# music_box.net
KiCad netlist of a schematic drawn in EAGLE
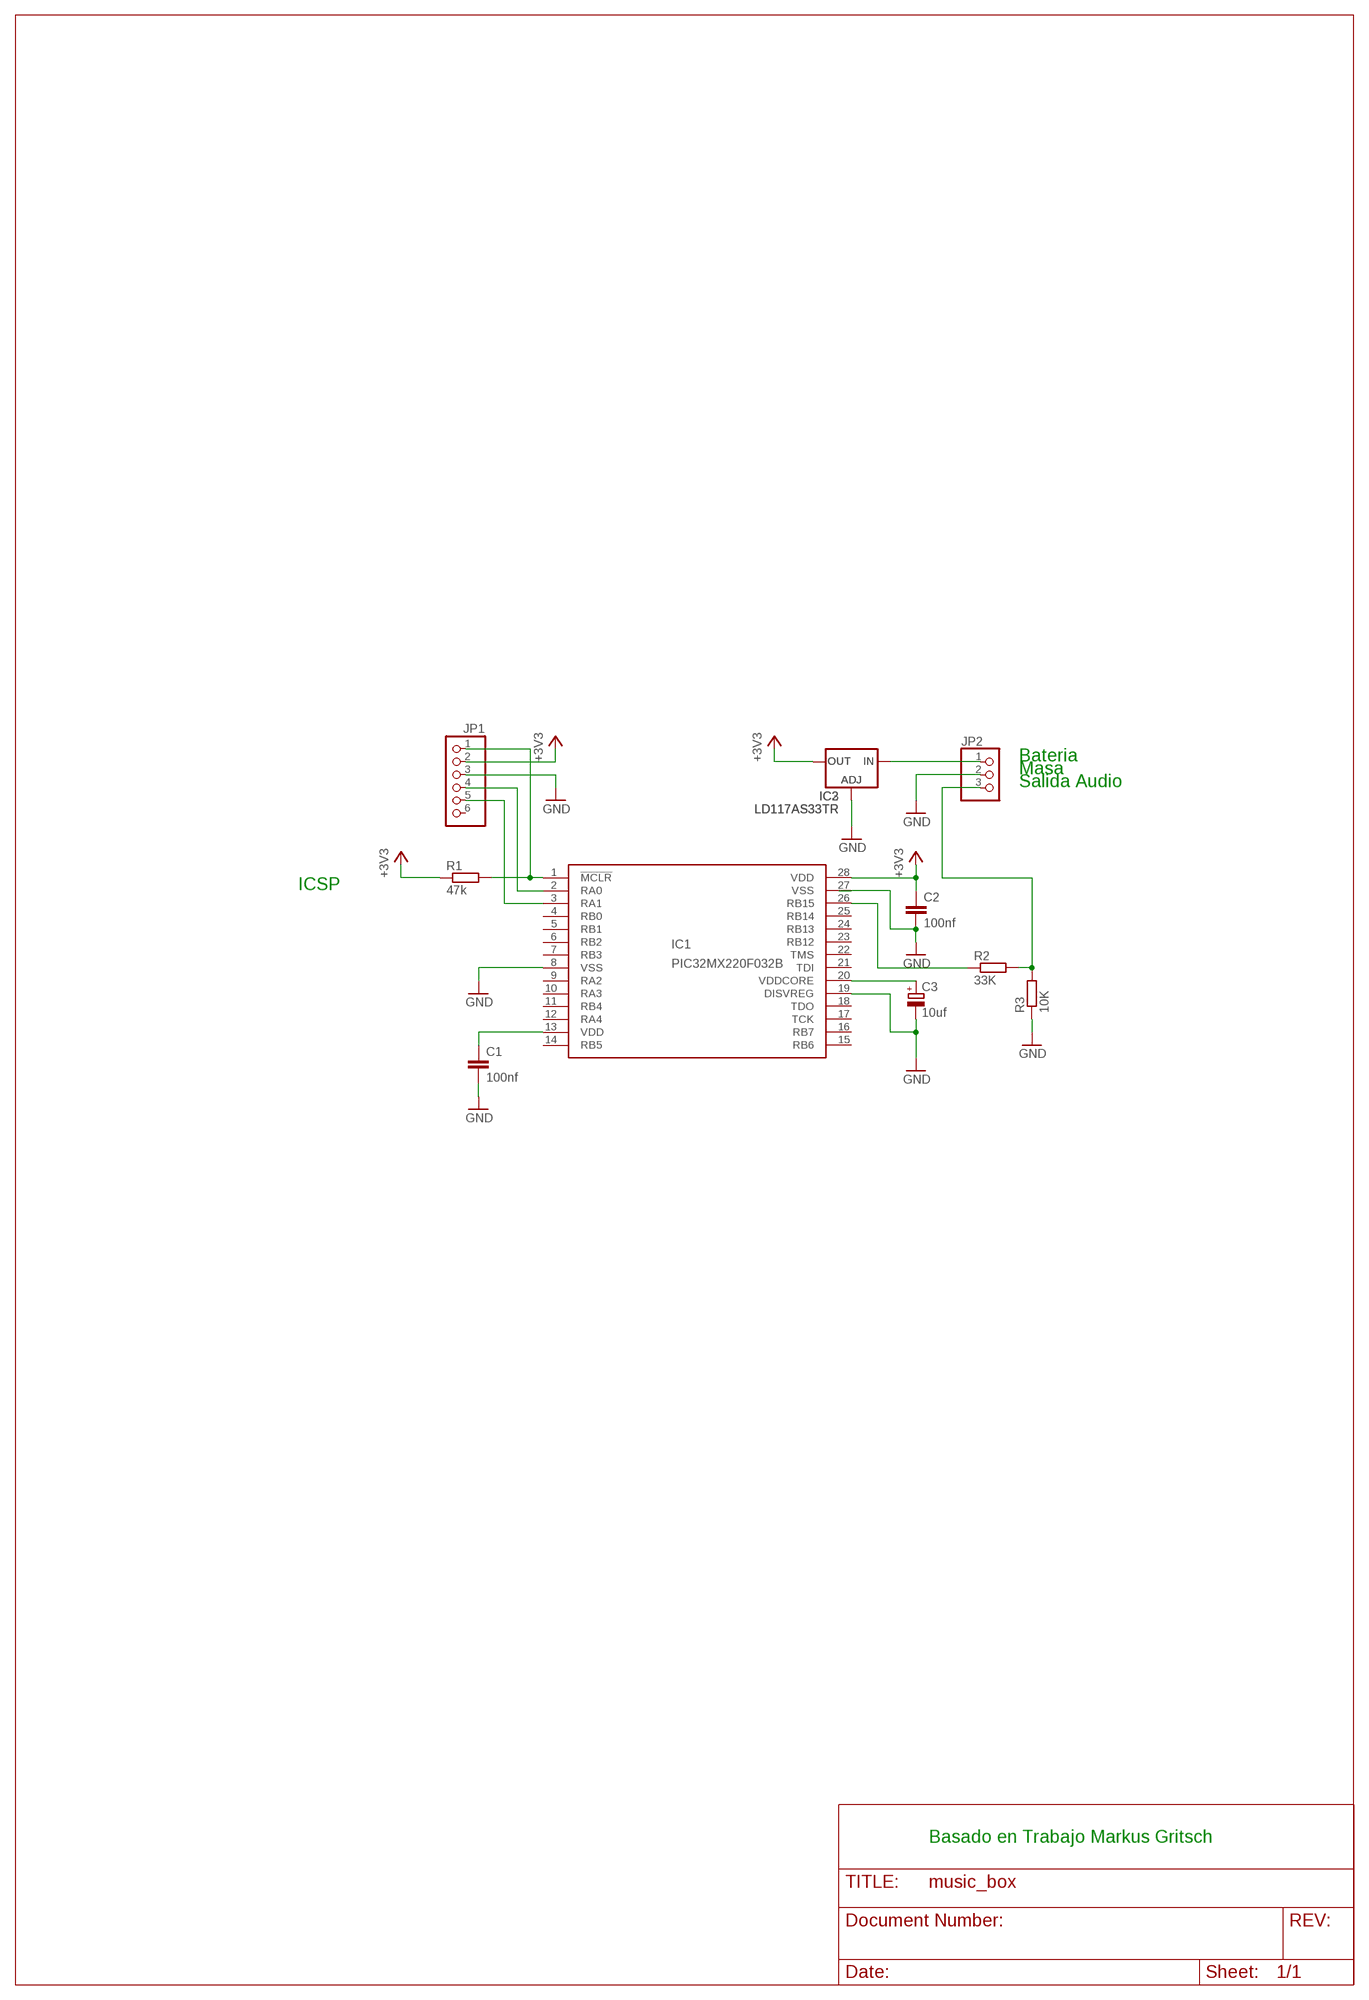
[diagram p0: schematic, sheet 1]

(export (version "E")
  (design (tool "Eeschema 10.0.6"))
  (components
    (comp (ref "C1")
      (value "100nf")
      (footprint "eagle-import:C025-024X044")
      (libsource (lib "eagle-import") (part "C-EU025-024X044"))
    )
    (comp (ref "C2")
      (value "100nf")
      (footprint "eagle-import:C025-024X044")
      (libsource (lib "eagle-import") (part "C-EU025-024X044"))
    )
    (comp (ref "C3")
      (value "10uf")
      (footprint "eagle-import:C_6032-28W")
      (libsource (lib "eagle-import") (part "CPOL-EUC/6032-28W"))
    )
    (comp (ref "IC1")
      (value "PIC32MX220F032B")
      (footprint "eagle-import:DIL28-3")
      (fields (field (name "MPN") "PIC24FJ32GA002-I/SP") (field (name "MPN_1") "PIC32MX220F032B-I/SP"))
      (libsource (lib "eagle-import") (part "PIC24FJ32GA002"))
    )
    (comp (ref "IC2")
      (value "LD117AS33TR")
      (footprint "eagle-import:SOT223")
      (libsource (lib "eagle-import") (part "LD117A?S33TR"))
    )
    (comp (ref "IC3")
      (value "LD117AS33TR")
      (footprint "eagle-import:SOT223")
      (libsource (lib "eagle-import") (part "LD117A?S33TR"))
    )
    (comp (ref "JP1")
      (value "PINHD-1X6")
      (footprint "eagle-import:1X06")
      (libsource (lib "eagle-import") (part "PINHD-1X6"))
    )
    (comp (ref "JP2")
      (value "PINHD-1X3")
      (footprint "eagle-import:1X03")
      (libsource (lib "eagle-import") (part "PINHD-1X3"))
    )
    (comp (ref "R1")
      (value "47k")
      (footprint "eagle-import:0204_5")
      (libsource (lib "eagle-import") (part "R-EU_0204/5"))
    )
    (comp (ref "R2")
      (value "33K")
      (footprint "eagle-import:0204_5")
      (libsource (lib "eagle-import") (part "R-EU_0204/5"))
    )
    (comp (ref "R3")
      (value "10K")
      (footprint "eagle-import:0204_5")
      (libsource (lib "eagle-import") (part "R-EU_0204/5"))
    )
  )
  (nets
    (net (code "1") (name "+3V3") (class "Default")
      (node (ref "C2") (pin "1") (pinfunction "1_1") (pintype "passive"))
      (node (ref "IC1") (pin "28") (pinfunction "VDD_28") (pintype "power_in"))
      (node (ref "IC2") (pin "4") (pinfunction "OUT_4") (pintype "passive"))
      (node (ref "IC3") (pin "4") (pinfunction "OUT_4") (pintype "passive"))
      (node (ref "JP1") (pin "2") (pinfunction "2_2") (pintype "passive"))
      (node (ref "R1") (pin "1") (pinfunction "1_1") (pintype "passive"))
    )
    (net (code "2") (name "GND") (class "Default")
      (node (ref "C1") (pin "2") (pinfunction "2_2") (pintype "passive"))
      (node (ref "C2") (pin "2") (pinfunction "2_2") (pintype "passive"))
      (node (ref "C3") (pin "-") (pinfunction "-_-") (pintype "passive"))
      (node (ref "IC1") (pin "19") (pinfunction "DISVREG_19") (pintype "passive"))
      (node (ref "IC1") (pin "27") (pinfunction "VSS_27") (pintype "power_in"))
      (node (ref "IC1") (pin "8") (pinfunction "VSS_8") (pintype "power_in"))
      (node (ref "IC2") (pin "1") (pinfunction "ADJ_1") (pintype "input"))
      (node (ref "IC3") (pin "1") (pinfunction "ADJ_1") (pintype "input"))
      (node (ref "JP1") (pin "3") (pinfunction "3_3") (pintype "passive"))
      (node (ref "JP2") (pin "2") (pinfunction "2_2") (pintype "passive"))
      (node (ref "R3") (pin "1") (pinfunction "1_1") (pintype "passive"))
    )
    (net (code "3") (name "Net-(C1-Pad1)") (class "Default")
      (node (ref "C1") (pin "1") (pinfunction "1_1") (pintype "passive"))
      (node (ref "IC1") (pin "13") (pinfunction "VDD_13") (pintype "power_in"))
    )
    (net (code "4") (name "Net-(IC1-RA0)") (class "Default")
      (node (ref "IC1") (pin "2") (pinfunction "RA0_2") (pintype "bidirectional"))
      (node (ref "JP1") (pin "4") (pinfunction "4_4") (pintype "passive"))
    )
    (net (code "5") (name "Net-(IC1-RA1)") (class "Default")
      (node (ref "IC1") (pin "3") (pinfunction "RA1_3") (pintype "bidirectional"))
      (node (ref "JP1") (pin "5") (pinfunction "5_5") (pintype "passive"))
    )
    (net (code "6") (name "Net-(IC1-RB15)") (class "Default")
      (node (ref "IC1") (pin "26") (pinfunction "RB15_26") (pintype "bidirectional"))
      (node (ref "R2") (pin "1") (pinfunction "1_1") (pintype "passive"))
    )
    (net (code "7") (name "Net-(IC1-VDDCORE)") (class "Default")
      (node (ref "C3") (pin "+") (pinfunction "+_+") (pintype "passive"))
      (node (ref "IC1") (pin "20") (pinfunction "VDDCORE_20") (pintype "power_in"))
    )
    (net (code "8") (name "Net-(IC1-~{MCLR})") (class "Default")
      (node (ref "IC1") (pin "1") (pinfunction "~{MCLR}_1") (pintype "bidirectional"))
      (node (ref "JP1") (pin "1") (pinfunction "1_1") (pintype "passive"))
      (node (ref "R1") (pin "2") (pinfunction "2_2") (pintype "passive"))
    )
    (net (code "9") (name "Net-(IC2-IN)") (class "Default")
      (node (ref "IC2") (pin "3") (pinfunction "IN_3") (pintype "input"))
      (node (ref "IC3") (pin "3") (pinfunction "IN_3") (pintype "input"))
      (node (ref "JP2") (pin "1") (pinfunction "1_1") (pintype "passive"))
    )
    (net (code "10") (name "Net-(JP2-Pad3)") (class "Default")
      (node (ref "JP2") (pin "3") (pinfunction "3_3") (pintype "passive"))
      (node (ref "R2") (pin "2") (pinfunction "2_2") (pintype "passive"))
      (node (ref "R3") (pin "2") (pinfunction "2_2") (pintype "passive"))
    )
    (net (code "11") (name "unconnected-(IC1-RA2-Pad9)") (class "Default")
      (node (ref "IC1") (pin "9") (pinfunction "RA2_9") (pintype "bidirectional"))
    )
    (net (code "12") (name "unconnected-(IC1-RA3-Pad10)") (class "Default")
      (node (ref "IC1") (pin "10") (pinfunction "RA3_10") (pintype "bidirectional"))
    )
    (net (code "13") (name "unconnected-(IC1-RA4-Pad12)") (class "Default")
      (node (ref "IC1") (pin "12") (pinfunction "RA4_12") (pintype "bidirectional"))
    )
    (net (code "14") (name "unconnected-(IC1-RB0-Pad4)") (class "Default")
      (node (ref "IC1") (pin "4") (pinfunction "RB0_4") (pintype "bidirectional"))
    )
    (net (code "15") (name "unconnected-(IC1-RB1-Pad5)") (class "Default")
      (node (ref "IC1") (pin "5") (pinfunction "RB1_5") (pintype "bidirectional"))
    )
    (net (code "16") (name "unconnected-(IC1-RB2-Pad6)") (class "Default")
      (node (ref "IC1") (pin "6") (pinfunction "RB2_6") (pintype "bidirectional"))
    )
    (net (code "17") (name "unconnected-(IC1-RB3-Pad7)") (class "Default")
      (node (ref "IC1") (pin "7") (pinfunction "RB3_7") (pintype "bidirectional"))
    )
    (net (code "18") (name "unconnected-(IC1-RB4-Pad11)") (class "Default")
      (node (ref "IC1") (pin "11") (pinfunction "RB4_11") (pintype "bidirectional"))
    )
    (net (code "19") (name "unconnected-(IC1-RB5-Pad14)") (class "Default")
      (node (ref "IC1") (pin "14") (pinfunction "RB5_14") (pintype "bidirectional"))
    )
    (net (code "20") (name "unconnected-(IC1-RB6-Pad15)") (class "Default")
      (node (ref "IC1") (pin "15") (pinfunction "RB6_15") (pintype "bidirectional"))
    )
    (net (code "21") (name "unconnected-(IC1-RB7-Pad16)") (class "Default")
      (node (ref "IC1") (pin "16") (pinfunction "RB7_16") (pintype "bidirectional"))
    )
    (net (code "22") (name "unconnected-(IC1-RB12-Pad23)") (class "Default")
      (node (ref "IC1") (pin "23") (pinfunction "RB12_23") (pintype "bidirectional"))
    )
    (net (code "23") (name "unconnected-(IC1-RB13-Pad24)") (class "Default")
      (node (ref "IC1") (pin "24") (pinfunction "RB13_24") (pintype "bidirectional"))
    )
    (net (code "24") (name "unconnected-(IC1-RB14-Pad25)") (class "Default")
      (node (ref "IC1") (pin "25") (pinfunction "RB14_25") (pintype "bidirectional"))
    )
    (net (code "25") (name "unconnected-(IC1-TCK-Pad17)") (class "Default")
      (node (ref "IC1") (pin "17") (pinfunction "TCK_17") (pintype "input"))
    )
    (net (code "26") (name "unconnected-(IC1-TDI-Pad21)") (class "Default")
      (node (ref "IC1") (pin "21") (pinfunction "TDI_21") (pintype "input"))
    )
    (net (code "27") (name "unconnected-(IC1-TDO-Pad18)") (class "Default")
      (node (ref "IC1") (pin "18") (pinfunction "TDO_18") (pintype "output"))
    )
    (net (code "28") (name "unconnected-(IC1-TMS-Pad22)") (class "Default")
      (node (ref "IC1") (pin "22") (pinfunction "TMS_22") (pintype "input"))
    )
    (net (code "29") (name "unconnected-(JP1-Pad6)") (class "Default")
      (node (ref "JP1") (pin "6") (pinfunction "6_6") (pintype "passive"))
    )
  )
)
